# Tracer-1_1.net
KiCad netlist of a schematic drawn in EasyEDA Pro
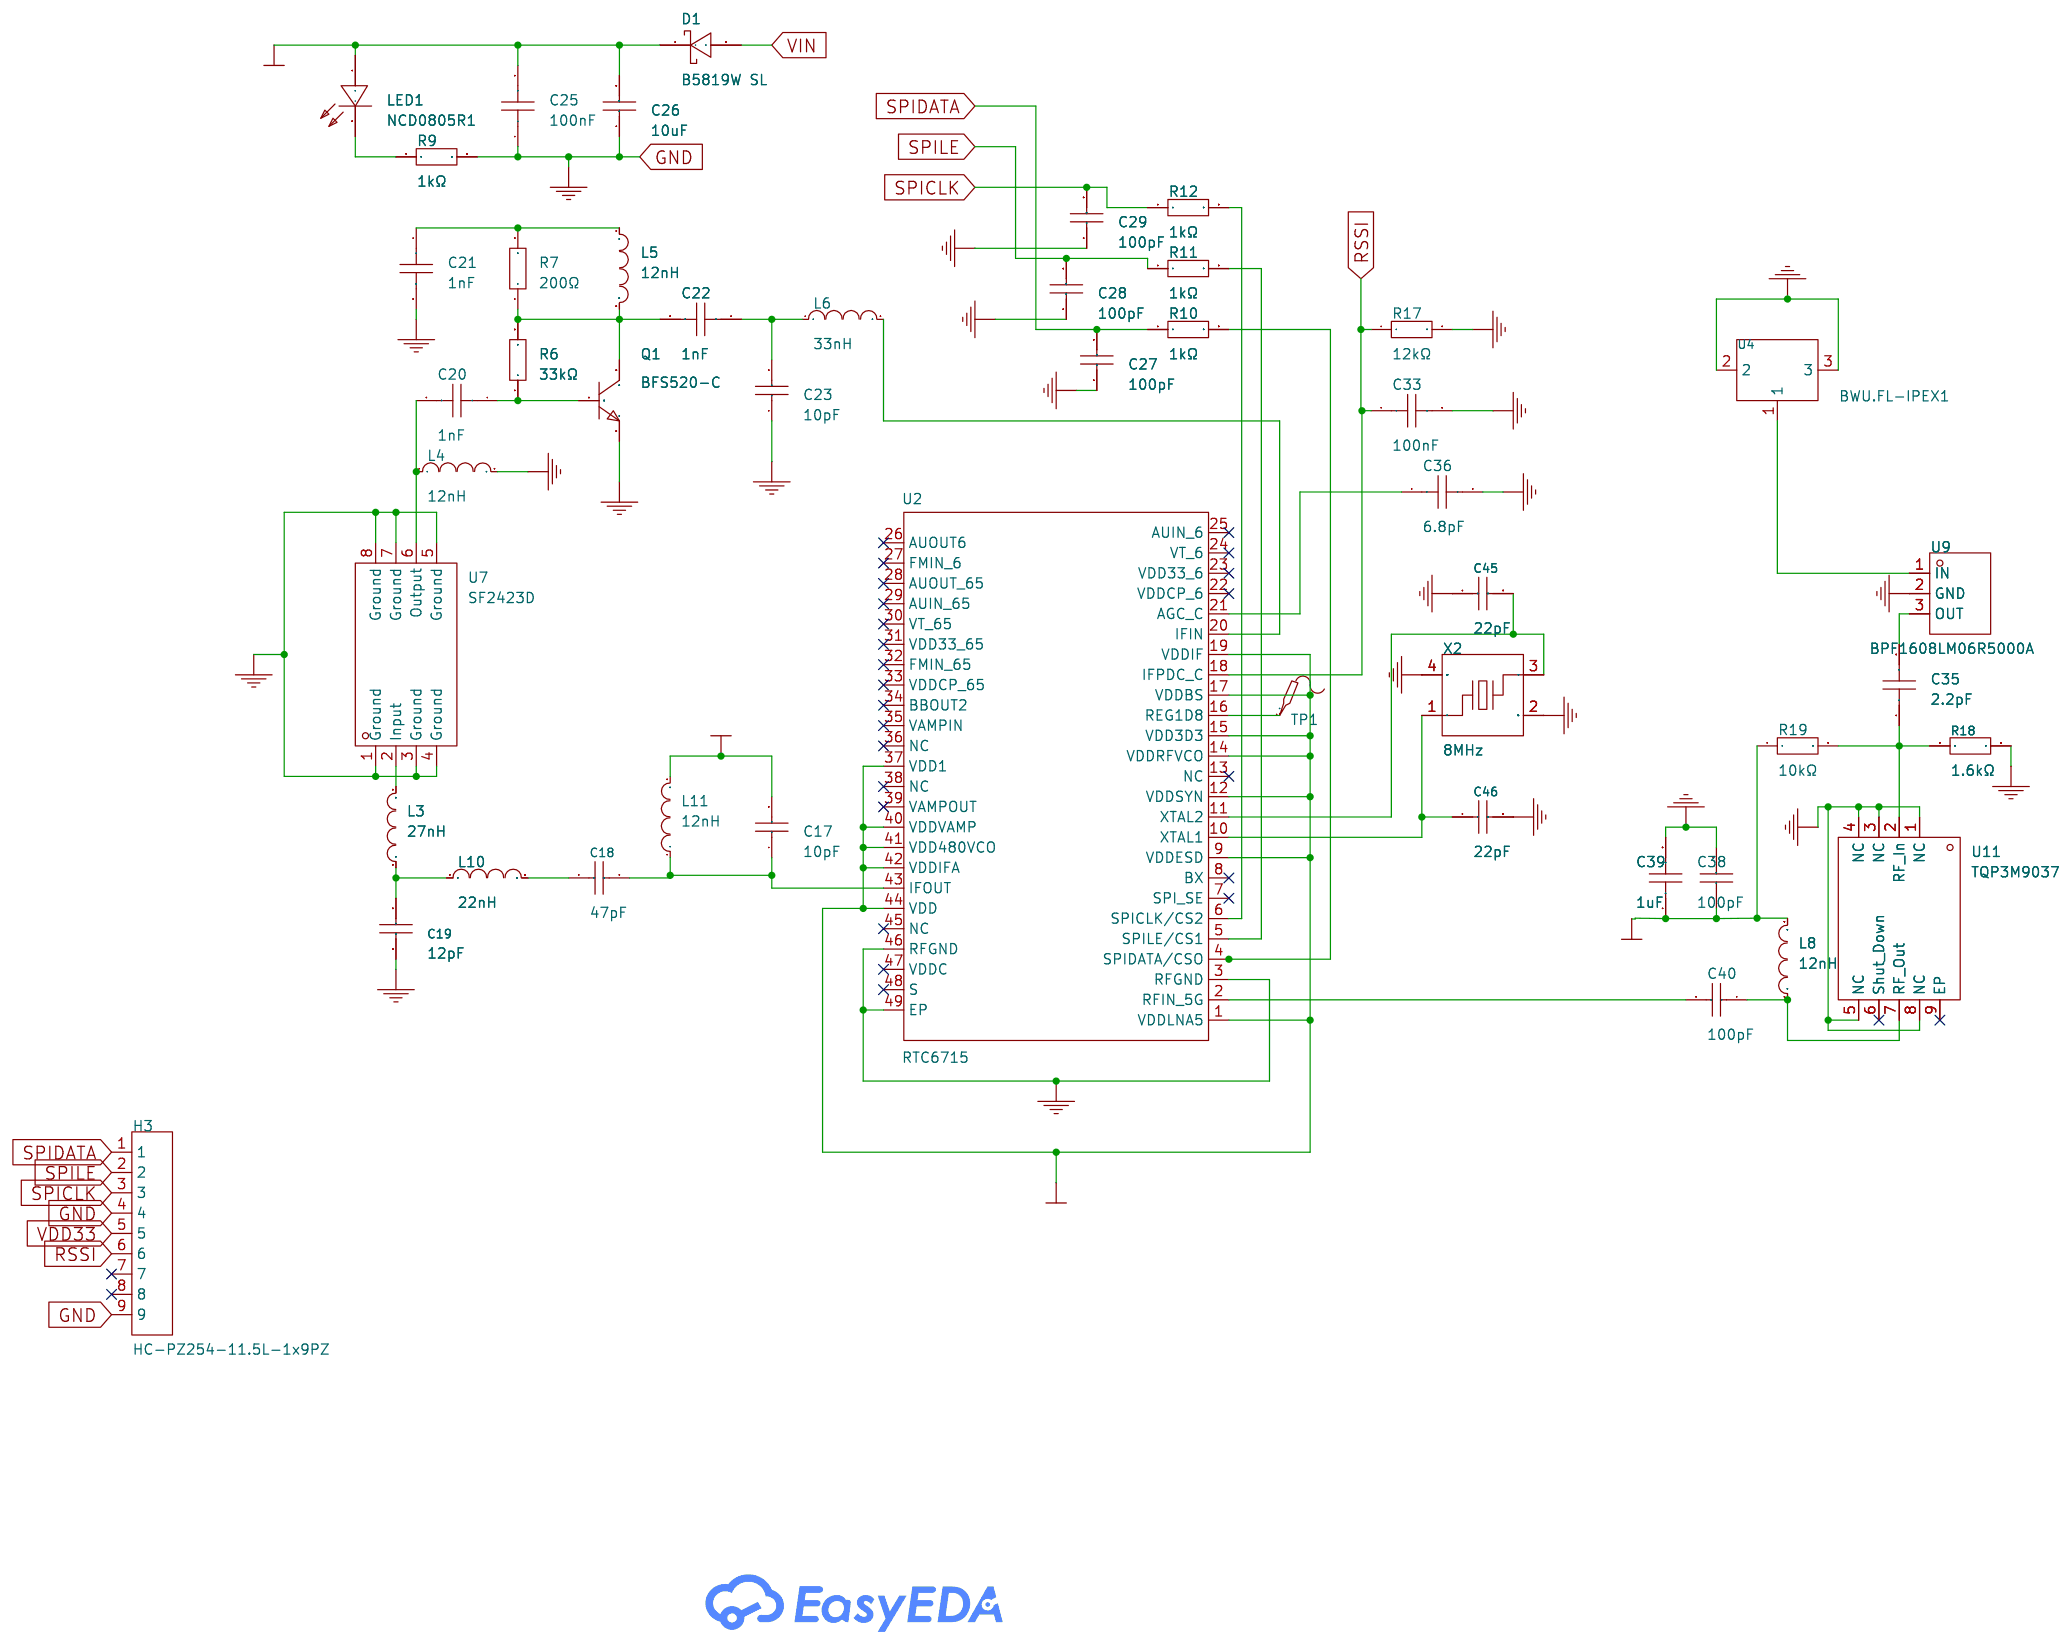
[diagram p0: schematic sheet]

(export (version "E")
  (design (tool "Eeschema 10.0.6"))
  (components
    (comp (ref "C17")
      (value "10pF")
      (footprint "easyedapro:C0402")
      (fields
        (field (name "Manufacturer Part") "CC0402JRNPO9BN100")
        (field (name "Manufacturer") "YAGEO(国巨)")
      )
      (libsource (lib "easyedapro") (part "CC0402JRNPO9BN100"))
    )
    (comp (ref "C18")
      (value "47pF")
      (footprint "easyedapro:C0402")
      (fields
        (field (name "Manufacturer Part") "CC0402JRNPO9BN470")
        (field (name "Manufacturer") "YAGEO(国巨)")
      )
      (libsource (lib "easyedapro") (part "CC0402JRNPO9BN470"))
    )
    (comp (ref "C19")
      (value "12pF")
      (footprint "easyedapro:C0402")
      (fields
        (field (name "Manufacturer Part") "GRM1555C1H120JA01D")
        (field (name "Manufacturer") "muRata(村田)")
      )
      (libsource (lib "easyedapro") (part "GRM1555C1H120JA01D"))
    )
    (comp (ref "C20")
      (value "1nF")
      (footprint "easyedapro:C0402")
      (fields
        (field (name "Manufacturer Part") "GRM155R71H102KA01D")
        (field (name "Manufacturer") "muRata(村田)")
      )
      (libsource (lib "easyedapro") (part "GRM155R71H102KA01D"))
    )
    (comp (ref "C21")
      (value "1nF")
      (footprint "easyedapro:C0402")
      (fields
        (field (name "Manufacturer Part") "GRM155R71H102KA01D")
        (field (name "Manufacturer") "muRata(村田)")
      )
      (libsource (lib "easyedapro") (part "GRM155R71H102KA01D"))
    )
    (comp (ref "C22")
      (value "1nF")
      (footprint "easyedapro:C0402")
      (fields
        (field (name "Manufacturer Part") "GRM155R71H102KA01D")
        (field (name "Manufacturer") "muRata(村田)")
      )
      (libsource (lib "easyedapro") (part "GRM155R71H102KA01D"))
    )
    (comp (ref "C23")
      (value "10pF")
      (footprint "easyedapro:C0402")
      (fields
        (field (name "Manufacturer Part") "GRM1555C1H100JA01D")
        (field (name "Manufacturer") "muRata(村田)")
      )
      (libsource (lib "easyedapro") (part "GRM1555C1H100JA01D"))
    )
    (comp (ref "C25")
      (value "100nF")
      (footprint "easyedapro:C0402")
      (fields
        (field (name "Manufacturer Part") "CL05B104KO5NNNC")
        (field (name "Manufacturer") "SAMSUNG(三星)")
      )
      (libsource (lib "easyedapro") (part "CL05B104KO5NNNC"))
    )
    (comp (ref "C26")
      (value "10uF")
      (fields
        (field (name "Manufacturer Part") "GRM155R60J106ME44D")
        (field (name "Manufacturer") "muRata(村田)")
      )
      (libsource (lib "easyedapro") (part "CL05A106MQ5NUNC"))
    )
    (comp (ref "C27")
      (value "100pF")
      (footprint "easyedapro:C0402")
      (fields
        (field (name "Manufacturer Part") "GRM1555C1H101JA01D")
        (field (name "Manufacturer") "muRata(村田)")
      )
      (libsource (lib "easyedapro") (part "GRM1555C1H101JA01D"))
    )
    (comp (ref "C28")
      (value "100pF")
      (footprint "easyedapro:C0402")
      (fields
        (field (name "Manufacturer Part") "GRM1555C1H101JA01D")
        (field (name "Manufacturer") "muRata(村田)")
      )
      (libsource (lib "easyedapro") (part "GRM1555C1H101JA01D"))
    )
    (comp (ref "C29")
      (value "100pF")
      (footprint "easyedapro:C0402")
      (fields
        (field (name "Manufacturer Part") "GRM1555C1H101JA01D")
        (field (name "Manufacturer") "muRata(村田)")
      )
      (libsource (lib "easyedapro") (part "GRM1555C1H101JA01D"))
    )
    (comp (ref "C33")
      (value "100nF")
      (footprint "easyedapro:C0402")
      (fields
        (field (name "Manufacturer Part") "CL05B104KO5NNNC")
        (field (name "Manufacturer") "SAMSUNG(三星)")
      )
      (libsource (lib "easyedapro") (part "CL05B104KO5NNNC"))
    )
    (comp (ref "C35")
      (value "2.2pF")
      (footprint "easyedapro:C0402")
      (fields
        (field (name "Manufacturer Part") "GJM1555C1H2R2BB01D")
        (field (name "Manufacturer") "muRata(村田)")
      )
      (libsource (lib "easyedapro") (part "GJM1555C1H2R2BB01D"))
    )
    (comp (ref "C36")
      (value "6.8pF")
      (footprint "easyedapro:C0402")
      (fields
        (field (name "Manufacturer Part") "CC0402CRNPO9BN6R8")
        (field (name "Manufacturer") "YAGEO(国巨)")
      )
      (libsource (lib "easyedapro") (part "CC0402CRNPO9BN6R8"))
    )
    (comp (ref "C38")
      (value "100pF")
      (footprint "easyedapro:C0402")
      (fields
        (field (name "Manufacturer Part") "GRM1555C1H101JA01D")
        (field (name "Manufacturer") "muRata(村田)")
      )
      (libsource (lib "easyedapro") (part "GRM1555C1H101JA01D"))
    )
    (comp (ref "C39")
      (value "1uF")
      (footprint "easyedapro:C0402")
      (fields
        (field (name "Manufacturer Part") "CL05A105KA5NQNC")
        (field (name "Manufacturer") "SAMSUNG(三星)")
      )
      (libsource (lib "easyedapro") (part "CL05A105KA5NQNC"))
    )
    (comp (ref "C40")
      (value "100pF")
      (footprint "easyedapro:C0402")
      (fields
        (field (name "Manufacturer Part") "GRM1555C1H101JA01D")
        (field (name "Manufacturer") "muRata(村田)")
      )
      (libsource (lib "easyedapro") (part "GRM1555C1H101JA01D"))
    )
    (comp (ref "C45")
      (value "22pF")
      (footprint "easyedapro:C0402")
      (fields
        (field (name "Manufacturer Part") "CC0402JRNPO9BN220")
        (field (name "Manufacturer") "YAGEO(国巨)")
      )
      (libsource (lib "easyedapro") (part "CC0402JRNPO9BN220"))
    )
    (comp (ref "C46")
      (value "22pF")
      (footprint "easyedapro:C0402")
      (fields
        (field (name "Manufacturer Part") "CC0402JRNPO9BN220")
        (field (name "Manufacturer") "YAGEO(国巨)")
      )
      (libsource (lib "easyedapro") (part "CC0402JRNPO9BN220"))
    )
    (comp (ref "D1")
      (value "B5819W SL")
      (footprint "easyedapro:SOD-123_L2.7-W1.6-LS3.7-RD-1")
      (description "Forward Voltage (Vf@If):600mV@1A Reverse Voltage (Vr):40V Rectified Current:1A")
      (fields (field (name "Manufacturer") "CJ(江苏长电/长晶)"))
      (libsource (lib "easyedapro") (part "B5819W_C8598"))
    )
    (comp (ref "H3")
      (value "HC-PZ254-11.5L-1x9PZ")
      (footprint "easyedapro:HDR-TH_9P-P2.54-V-M")
      (fields (field (name "Manufacturer") "HC(虹成电子)"))
      (libsource (lib "easyedapro") (part "HC-PZ254-11.5L-1X9PZ"))
    )
    (comp (ref "L3")
      (value "27nH")
      (footprint "easyedapro:L0402-RD")
      (fields (field (name "Manufacturer Part") "LQG15HS27NJ02D") (field (name "Manufacturer") "muRata(村田)"))
      (libsource (lib "easyedapro") (part "LQG15HS27NJ02D"))
    )
    (comp (ref "L4")
      (value "12nH")
      (footprint "easyedapro:L0402")
      (fields (field (name "Manufacturer Part") "LQW15AN12NG00D") (field (name "Manufacturer") "muRata(村田)"))
      (libsource (lib "easyedapro") (part "LQW15AN12NG00D"))
    )
    (comp (ref "L5")
      (value "12nH")
      (footprint "easyedapro:L0402")
      (fields (field (name "Manufacturer Part") "LQW15AN12NG00D") (field (name "Manufacturer") "muRata(村田)"))
      (libsource (lib "easyedapro") (part "LQW15AN12NG00D"))
    )
    (comp (ref "L6")
      (value "33nH")
      (footprint "easyedapro:L0402")
      (fields (field (name "Manufacturer Part") "LQG15HS33NJ02D") (field (name "Manufacturer") "muRata(村田)"))
      (libsource (lib "easyedapro") (part "LQG15HS33NJ02D"))
    )
    (comp (ref "L8")
      (value "12nH")
      (footprint "easyedapro:L0402")
      (fields (field (name "Manufacturer Part") "LQW15AN12NG00D") (field (name "Manufacturer") "muRata(村田)"))
      (libsource (lib "easyedapro") (part "LQW15AN12NG00D"))
    )
    (comp (ref "L10")
      (value "22nH")
      (footprint "easyedapro:L0402")
      (fields (field (name "Manufacturer Part") "LQW15AN22NJ00D") (field (name "Manufacturer") "muRata(村田)"))
      (libsource (lib "easyedapro") (part "LQW15AN22NJ00D"))
    )
    (comp (ref "L11")
      (value "12nH")
      (footprint "easyedapro:L0402")
      (fields (field (name "Manufacturer Part") "LQW15AN12NG00D") (field (name "Manufacturer") "muRata(村田)"))
      (libsource (lib "easyedapro") (part "LQW15AN12NG00D"))
    )
    (comp (ref "LED1")
      (value "NCD0805R1")
      (footprint "easyedapro:LED0805-R-RD")
      (fields (field (name "Manufacturer") "国星光电"))
      (libsource (lib "easyedapro") (part "FC-2012HRK-620D"))
    )
    (comp (ref "Q1")
      (value "BFS520-C")
      (footprint "easyedapro:SOT-323-3_L2.0-W1.3-P1.30-LS2.3-BR")
      (fields (field (name "Manufacturer") "Slkor(萨科微)"))
      (libsource (lib "easyedapro") (part "BFS520-C"))
    )
    (comp (ref "R6")
      (value "33kΩ")
      (footprint "easyedapro:R0402")
      (fields (field (name "Manufacturer Part") "RC0402FR-0733KL") (field (name "Manufacturer") "YAGEO(国巨)"))
      (libsource (lib "easyedapro") (part "RC0402FR-0733KL"))
    )
    (comp (ref "R7")
      (value "200Ω")
      (footprint "easyedapro:R0402")
      (fields (field (name "Manufacturer Part") "RC0402FR-07200RL") (field (name "Manufacturer") "YAGEO(国巨)"))
      (libsource (lib "easyedapro") (part "RC0402FR-07200RL"))
    )
    (comp (ref "R9")
      (value "1kΩ")
      (footprint "easyedapro:R0402")
      (fields (field (name "Manufacturer Part") "RC0402FR-071KL") (field (name "Manufacturer") "YAGEO(国巨)"))
      (libsource (lib "easyedapro") (part "RC0402FR-071KL"))
    )
    (comp (ref "R10")
      (value "1kΩ")
      (footprint "easyedapro:R0402")
      (fields (field (name "Manufacturer Part") "RC0402FR-071KL") (field (name "Manufacturer") "YAGEO(国巨)"))
      (libsource (lib "easyedapro") (part "RC0402FR-071KL"))
    )
    (comp (ref "R11")
      (value "1kΩ")
      (footprint "easyedapro:R0402")
      (fields (field (name "Manufacturer Part") "RC0402FR-071KL") (field (name "Manufacturer") "YAGEO(国巨)"))
      (libsource (lib "easyedapro") (part "RC0402FR-071KL"))
    )
    (comp (ref "R12")
      (value "1kΩ")
      (footprint "easyedapro:R0402")
      (fields (field (name "Manufacturer Part") "RC0402FR-071KL") (field (name "Manufacturer") "YAGEO(国巨)"))
      (libsource (lib "easyedapro") (part "RC0402FR-071KL"))
    )
    (comp (ref "R17")
      (value "12kΩ")
      (footprint "easyedapro:R0402")
      (fields (field (name "Manufacturer Part") "RTT021202FTH") (field (name "Manufacturer") "RALEC(旺诠)"))
      (libsource (lib "easyedapro") (part "RTT021202FTH"))
    )
    (comp (ref "R18")
      (value "1.6kΩ")
      (footprint "easyedapro:R0402")
      (fields
        (field (name "Manufacturer Part") "0402WGF1601TCE")
        (field (name "Manufacturer") "UNI-ROYAL(厚声)")
      )
      (libsource (lib "easyedapro") (part "0402WGF1601TCE"))
    )
    (comp (ref "R19")
      (value "10kΩ")
      (footprint "easyedapro:R0402")
      (fields
        (field (name "Manufacturer Part") "0402WGF1002TCE")
        (field (name "Manufacturer") "UNI-ROYAL(厚声)")
      )
      (libsource (lib "easyedapro") (part "0402WGF1002TCE"))
    )
    (comp (ref "TP1")
      (value "~")
      (footprint "easyedapro:Test-Point-0.5mm")
      (description "Test Point 测试点")
      (libsource (lib "easyedapro") (part "Test-Point"))
    )
    (comp (ref "U2") (value "RTC6715") (libsource (lib "easyedapro") (part "RTC6715")))
    (comp (ref "U4")
      (value "BWU.FL-IPEX1")
      (footprint "easyedapro:IPEX-SMD_BWIPX-1-001E")
      (fields (field (name "Manufacturer") "BAT WIRELESS(蝙蝠无线)"))
      (libsource (lib "easyedapro") (part "BWU.FL-IPEX1"))
    )
    (comp (ref "U7")
      (value "SF2423D")
      (footprint "easyedapro:FILTER-SMD_8P-L3.8-W3.8-P1.27-BL")
      (fields (field (name "Manufacturer") "muRata(村田)"))
      (libsource (lib "easyedapro") (part "SF2423D"))
    )
    (comp (ref "U9")
      (value "BPF1608LM06R5000A")
      (footprint "easyedapro:FILTER-SMD_3P-L1.6-W0.8-L")
      (description "Bandwidth:800MHz Filter Type:Bandpass Insertion Loss:0.6dB")
      (fields (field (name "Manufacturer") "YAGEO(国巨)"))
      (libsource (lib "easyedapro") (part "BPF1608LM06R5000A"))
    )
    (comp (ref "U11")
      (value "TQP3M9037")
      (footprint "easyedapro:DFN-8_L2.0-W2.0-P0.50-BL-EP")
      (fields (field (name "Manufacturer") "Qorvo"))
      (libsource (lib "easyedapro") (part "TQP3M9037"))
    )
    (comp (ref "X2")
      (value "8MHz")
      (footprint "easyedapro:CRYSTAL-SMD_4P-L3.2-W2.5-BL")
      (fields (field (name "Manufacturer Part") "K3A080001210") (field (name "Manufacturer") "KYX(凯越翔)"))
      (libsource (lib "easyedapro") (part "K3A080001210"))
    )
  )
  (nets
    (net (code "1") (name "GND") (class "Default")
      (node (ref "C19") (pin "1") (pinfunction "1_1") (pintype "input"))
      (node (ref "C21") (pin "2") (pinfunction "2_2") (pintype "unspecified"))
      (node (ref "C23") (pin "1") (pinfunction "1_1") (pintype "input"))
      (node (ref "C25") (pin "1") (pinfunction "1_1") (pintype "unspecified"))
      (node (ref "C26") (pin "1") (pinfunction "1_1") (pintype "input"))
      (node (ref "C27") (pin "1") (pinfunction "1_1") (pintype "input"))
      (node (ref "C28") (pin "1") (pinfunction "1_1") (pintype "input"))
      (node (ref "C29") (pin "1") (pinfunction "1_1") (pintype "input"))
      (node (ref "C33") (pin "2") (pinfunction "2_2") (pintype "unspecified"))
      (node (ref "C36") (pin "2") (pinfunction "2_2") (pintype "unspecified"))
      (node (ref "C38") (pin "2") (pinfunction "2_2") (pintype "input"))
      (node (ref "C39") (pin "2") (pinfunction "2_2") (pintype "unspecified"))
      (node (ref "C45") (pin "1") (pinfunction "1_1") (pintype "input"))
      (node (ref "C46") (pin "2") (pinfunction "2_2") (pintype "input"))
      (node (ref "H3") (pin "4") (pinfunction "4_4") (pintype "unspecified"))
      (node (ref "H3") (pin "9") (pinfunction "9_9") (pintype "unspecified"))
      (node (ref "L4") (pin "2") (pinfunction "2_2") (pintype "unspecified"))
      (node (ref "Q1") (pin "2") (pinfunction "E_2") (pintype "input"))
      (node (ref "R17") (pin "2") (pinfunction "2_2") (pintype "input"))
      (node (ref "R18") (pin "2") (pinfunction "2_2") (pintype "input"))
      (node (ref "R9") (pin "2") (pinfunction "2_2") (pintype "input"))
      (node (ref "U11") (pin "1") (pinfunction "NC_1") (pintype "unspecified"))
      (node (ref "U11") (pin "3") (pinfunction "NC_3") (pintype "unspecified"))
      (node (ref "U11") (pin "4") (pinfunction "NC_4") (pintype "unspecified"))
      (node (ref "U11") (pin "5") (pinfunction "NC_5") (pintype "unspecified"))
      (node (ref "U11") (pin "8") (pinfunction "NC_8") (pintype "unspecified"))
      (node (ref "U2") (pin "3") (pinfunction "RFGND_3") (pintype "unspecified"))
      (node (ref "U2") (pin "46") (pinfunction "RFGND_46") (pintype "unspecified"))
      (node (ref "U2") (pin "49") (pinfunction "EP_49") (pintype "unspecified"))
      (node (ref "U4") (pin "2") (pinfunction "2_2") (pintype "input"))
      (node (ref "U4") (pin "3") (pinfunction "3_3") (pintype "input"))
      (node (ref "U7") (pin "1") (pinfunction "Ground_1") (pintype "unspecified"))
      (node (ref "U7") (pin "3") (pinfunction "Ground_3") (pintype "unspecified"))
      (node (ref "U7") (pin "4") (pinfunction "Ground_4") (pintype "unspecified"))
      (node (ref "U7") (pin "5") (pinfunction "Ground_5") (pintype "unspecified"))
      (node (ref "U7") (pin "7") (pinfunction "Ground_7") (pintype "unspecified"))
      (node (ref "U7") (pin "8") (pinfunction "Ground_8") (pintype "unspecified"))
      (node (ref "U9") (pin "2") (pinfunction "GND_2") (pintype "unspecified"))
      (node (ref "X2") (pin "2") (pinfunction "GND_2") (pintype "input"))
      (node (ref "X2") (pin "4") (pinfunction "GND_4") (pintype "input"))
    )
    (net (code "2") (name "Net-(C18-Pad1)") (class "Default")
      (node (ref "C18") (pin "1") (pinfunction "1_1") (pintype "input"))
      (node (ref "L10") (pin "2") (pinfunction "2_2") (pintype "unspecified"))
    )
    (net (code "3") (name "Net-(C19-Pad2)") (class "Default")
      (node (ref "C19") (pin "2") (pinfunction "2_2") (pintype "input"))
      (node (ref "L10") (pin "1") (pinfunction "1_1") (pintype "unspecified"))
      (node (ref "L3") (pin "1") (pinfunction "1_1") (pintype "unspecified"))
    )
    (net (code "4") (name "Net-(C21-Pad1)") (class "Default")
      (node (ref "C21") (pin "1") (pinfunction "1_1") (pintype "unspecified"))
      (node (ref "L5") (pin "1") (pinfunction "1_1") (pintype "unspecified"))
      (node (ref "R7") (pin "2") (pinfunction "2_2") (pintype "input"))
    )
    (net (code "5") (name "Net-(C22-Pad1)") (class "Default")
      (node (ref "C22") (pin "1") (pinfunction "1_1") (pintype "unspecified"))
      (node (ref "C23") (pin "2") (pinfunction "2_2") (pintype "input"))
      (node (ref "L6") (pin "1") (pinfunction "1_1") (pintype "unspecified"))
    )
    (net (code "6") (name "Net-(LED1--)") (class "Default")
      (node (ref "LED1") (pin "2") (pinfunction "-_2") (pintype "unspecified"))
      (node (ref "R9") (pin "1") (pinfunction "1_1") (pintype "input"))
    )
    (net (code "7") (name "Net-(Q1-B)") (class "Default")
      (node (ref "C20") (pin "1") (pinfunction "1_1") (pintype "unspecified"))
      (node (ref "Q1") (pin "1") (pinfunction "B_1") (pintype "input"))
      (node (ref "R6") (pin "1") (pinfunction "1_1") (pintype "input"))
    )
    (net (code "8") (name "Net-(Q1-C)") (class "Default")
      (node (ref "C22") (pin "2") (pinfunction "2_2") (pintype "unspecified"))
      (node (ref "L5") (pin "2") (pinfunction "2_2") (pintype "unspecified"))
      (node (ref "Q1") (pin "3") (pinfunction "C_3") (pintype "input"))
      (node (ref "R6") (pin "2") (pinfunction "2_2") (pintype "input"))
      (node (ref "R7") (pin "1") (pinfunction "1_1") (pintype "input"))
    )
    (net (code "9") (name "Net-(U2-AGC_C)") (class "Default")
      (node (ref "C36") (pin "1") (pinfunction "1_1") (pintype "unspecified"))
      (node (ref "U2") (pin "21") (pinfunction "AGC_C_21") (pintype "unspecified"))
    )
    (net (code "10") (name "Net-(U2-IFIN)") (class "Default")
      (node (ref "L6") (pin "2") (pinfunction "2_2") (pintype "unspecified"))
      (node (ref "U2") (pin "20") (pinfunction "IFIN_20") (pintype "unspecified"))
    )
    (net (code "11") (name "Net-(U2-IFOUT)") (class "Default")
      (node (ref "C17") (pin "1") (pinfunction "1_1") (pintype "input"))
      (node (ref "C18") (pin "2") (pinfunction "2_2") (pintype "input"))
      (node (ref "L11") (pin "1") (pinfunction "1_1") (pintype "unspecified"))
      (node (ref "U2") (pin "43") (pinfunction "IFOUT_43") (pintype "unspecified"))
    )
    (net (code "12") (name "Net-(U2-REG1D8)") (class "Default")
      (node (ref "TP1") (pin "1") (pinfunction "1_1") (pintype "unspecified"))
      (node (ref "U2") (pin "16") (pinfunction "REG1D8_16") (pintype "unspecified"))
    )
    (net (code "13") (name "Net-(U2-RFIN_5G)") (class "Default")
      (node (ref "C40") (pin "2") (pinfunction "2_2") (pintype "input"))
      (node (ref "U2") (pin "2") (pinfunction "RFIN_5G_2") (pintype "unspecified"))
    )
    (net (code "14") (name "Net-(U2-SPICLK{slash}CS2)") (class "Default")
      (node (ref "R12") (pin "2") (pinfunction "2_2") (pintype "input"))
      (node (ref "U2") (pin "6") (pinfunction "SPICLK/CS2_6") (pintype "unspecified"))
    )
    (net (code "15") (name "Net-(U2-SPIDATA{slash}CSO)") (class "Default")
      (node (ref "R10") (pin "2") (pinfunction "2_2") (pintype "input"))
      (node (ref "U2") (pin "4") (pinfunction "SPIDATA/CSO_4") (pintype "unspecified"))
    )
    (net (code "16") (name "Net-(U2-SPILE{slash}CS1)") (class "Default")
      (node (ref "R11") (pin "2") (pinfunction "2_2") (pintype "input"))
      (node (ref "U2") (pin "5") (pinfunction "SPILE/CS1_5") (pintype "unspecified"))
    )
    (net (code "17") (name "Net-(U2-XTAL1)") (class "Default")
      (node (ref "C46") (pin "1") (pinfunction "1_1") (pintype "input"))
      (node (ref "U2") (pin "10") (pinfunction "XTAL1_10") (pintype "unspecified"))
      (node (ref "X2") (pin "1") (pinfunction "1_1") (pintype "input"))
    )
    (net (code "18") (name "Net-(U2-XTAL2)") (class "Default")
      (node (ref "C45") (pin "2") (pinfunction "2_2") (pintype "input"))
      (node (ref "U2") (pin "11") (pinfunction "XTAL2_11") (pintype "unspecified"))
      (node (ref "X2") (pin "3") (pinfunction "3_3") (pintype "input"))
    )
    (net (code "19") (name "Net-(U7-Input)") (class "Default")
      (node (ref "L3") (pin "2") (pinfunction "2_2") (pintype "unspecified"))
      (node (ref "U7") (pin "2") (pinfunction "Input_2") (pintype "unspecified"))
    )
    (net (code "20") (name "Net-(U7-Output)") (class "Default")
      (node (ref "C20") (pin "2") (pinfunction "2_2") (pintype "unspecified"))
      (node (ref "L4") (pin "1") (pinfunction "1_1") (pintype "unspecified"))
      (node (ref "U7") (pin "6") (pinfunction "Output_6") (pintype "unspecified"))
    )
    (net (code "21") (name "Net-(U9-IN)") (class "Default")
      (node (ref "U4") (pin "1") (pinfunction "1_1") (pintype "input"))
      (node (ref "U9") (pin "1") (pinfunction "IN_1") (pintype "unspecified"))
    )
    (net (code "22") (name "Net-(U9-OUT)") (class "Default")
      (node (ref "C35") (pin "2") (pinfunction "2_2") (pintype "unspecified"))
      (node (ref "U9") (pin "3") (pinfunction "OUT_3") (pintype "unspecified"))
    )
    (net (code "23") (name "Net-(U11-RF_In)") (class "Default")
      (node (ref "C35") (pin "1") (pinfunction "1_1") (pintype "unspecified"))
      (node (ref "R18") (pin "1") (pinfunction "1_1") (pintype "input"))
      (node (ref "R19") (pin "2") (pinfunction "2_2") (pintype "input"))
      (node (ref "U11") (pin "2") (pinfunction "RF_In_2") (pintype "unspecified"))
    )
    (net (code "24") (name "Net-(U11-RF_Out)") (class "Default")
      (node (ref "C40") (pin "1") (pinfunction "1_1") (pintype "input"))
      (node (ref "L8") (pin "1") (pinfunction "1_1") (pintype "unspecified"))
      (node (ref "U11") (pin "7") (pinfunction "RF_Out_7") (pintype "unspecified"))
    )
    (net (code "25") (name "RSSI") (class "Default")
      (node (ref "C33") (pin "1") (pinfunction "1_1") (pintype "unspecified"))
      (node (ref "H3") (pin "6") (pinfunction "6_6") (pintype "unspecified"))
      (node (ref "R17") (pin "1") (pinfunction "1_1") (pintype "input"))
      (node (ref "U2") (pin "18") (pinfunction "IFPDC_C_18") (pintype "unspecified"))
    )
    (net (code "26") (name "SPICLK") (class "Default")
      (node (ref "C29") (pin "2") (pinfunction "2_2") (pintype "input"))
      (node (ref "H3") (pin "3") (pinfunction "3_3") (pintype "unspecified"))
      (node (ref "R12") (pin "1") (pinfunction "1_1") (pintype "input"))
    )
    (net (code "27") (name "SPIDATA") (class "Default")
      (node (ref "C27") (pin "2") (pinfunction "2_2") (pintype "input"))
      (node (ref "H3") (pin "1") (pinfunction "1_1") (pintype "unspecified"))
      (node (ref "R10") (pin "1") (pinfunction "1_1") (pintype "input"))
    )
    (net (code "28") (name "SPILE") (class "Default")
      (node (ref "C28") (pin "2") (pinfunction "2_2") (pintype "input"))
      (node (ref "H3") (pin "2") (pinfunction "2_2") (pintype "unspecified"))
      (node (ref "R11") (pin "1") (pinfunction "1_1") (pintype "input"))
    )
    (net (code "29") (name "VDD33") (class "Default")
      (node (ref "C17") (pin "2") (pinfunction "2_2") (pintype "input"))
      (node (ref "C25") (pin "2") (pinfunction "2_2") (pintype "unspecified"))
      (node (ref "C26") (pin "2") (pinfunction "2_2") (pintype "input"))
      (node (ref "C38") (pin "1") (pinfunction "1_1") (pintype "input"))
      (node (ref "C39") (pin "1") (pinfunction "1_1") (pintype "unspecified"))
      (node (ref "D1") (pin "1") (pinfunction "-_1") (pintype "unspecified"))
      (node (ref "H3") (pin "5") (pinfunction "5_5") (pintype "unspecified"))
      (node (ref "L11") (pin "2") (pinfunction "2_2") (pintype "unspecified"))
      (node (ref "LED1") (pin "1") (pinfunction "+_1") (pintype "unspecified"))
      (node (ref "R19") (pin "1") (pinfunction "1_1") (pintype "input"))
      (node (ref "U2") (pin "1") (pinfunction "VDDLNA5_1") (pintype "unspecified"))
      (node (ref "U2") (pin "12") (pinfunction "VDDSYN_12") (pintype "unspecified"))
      (node (ref "U2") (pin "14") (pinfunction "VDDRFVCO_14") (pintype "unspecified"))
      (node (ref "U2") (pin "15") (pinfunction "VDD3D3_15") (pintype "unspecified"))
      (node (ref "U2") (pin "17") (pinfunction "VDDBS_17") (pintype "unspecified"))
      (node (ref "U2") (pin "19") (pinfunction "VDDIF_19") (pintype "unspecified"))
      (node (ref "U2") (pin "37") (pinfunction "VDD1_37") (pintype "unspecified"))
      (node (ref "U2") (pin "40") (pinfunction "VDDVAMP_40") (pintype "unspecified"))
      (node (ref "U2") (pin "41") (pinfunction "VDD480VCO_41") (pintype "unspecified"))
      (node (ref "U2") (pin "42") (pinfunction "VDDIFA_42") (pintype "unspecified"))
      (node (ref "U2") (pin "44") (pinfunction "VDD_44") (pintype "unspecified"))
      (node (ref "U2") (pin "9") (pinfunction "VDDESD_9") (pintype "unspecified"))
    )
    (net (code "30") (name "VIN") (class "Default")
      (node (ref "D1") (pin "2") (pinfunction "+_2") (pintype "unspecified"))
    )
    (net (code "31") (name "unconnected-(H3-Pad7)") (class "Default")
      (node (ref "H3") (pin "7") (pinfunction "7_7") (pintype "unspecified+no_connect"))
    )
    (net (code "32") (name "unconnected-(H3-Pad8)") (class "Default")
      (node (ref "H3") (pin "8") (pinfunction "8_8") (pintype "unspecified+no_connect"))
    )
    (net (code "33") (name "unconnected-(L8-Pad2)") (class "Default")
      (node (ref "L8") (pin "2") (pinfunction "2_2") (pintype "unspecified"))
    )
    (net (code "34") (name "unconnected-(U2-AUIN_6-Pad25)") (class "Default")
      (node (ref "U2") (pin "25") (pinfunction "AUIN_6_25") (pintype "unspecified+no_connect"))
    )
    (net (code "35") (name "unconnected-(U2-AUIN_65-Pad29)") (class "Default")
      (node (ref "U2") (pin "29") (pinfunction "AUIN_65_29") (pintype "unspecified+no_connect"))
    )
    (net (code "36") (name "unconnected-(U2-AUOUT6-Pad26)") (class "Default")
      (node (ref "U2") (pin "26") (pinfunction "AUOUT6_26") (pintype "unspecified+no_connect"))
    )
    (net (code "37") (name "unconnected-(U2-AUOUT_65-Pad28)") (class "Default")
      (node (ref "U2") (pin "28") (pinfunction "AUOUT_65_28") (pintype "unspecified+no_connect"))
    )
    (net (code "38") (name "unconnected-(U2-BBOUT2-Pad34)") (class "Default")
      (node (ref "U2") (pin "34") (pinfunction "BBOUT2_34") (pintype "unspecified+no_connect"))
    )
    (net (code "39") (name "unconnected-(U2-BX-Pad8)") (class "Default")
      (node (ref "U2") (pin "8") (pinfunction "BX_8") (pintype "unspecified+no_connect"))
    )
    (net (code "40") (name "unconnected-(U2-FMIN_6-Pad27)") (class "Default")
      (node (ref "U2") (pin "27") (pinfunction "FMIN_6_27") (pintype "unspecified+no_connect"))
    )
    (net (code "41") (name "unconnected-(U2-FMIN_65-Pad32)") (class "Default")
      (node (ref "U2") (pin "32") (pinfunction "FMIN_65_32") (pintype "unspecified+no_connect"))
    )
    (net (code "42") (name "unconnected-(U2-NC-Pad13)") (class "Default")
      (node (ref "U2") (pin "13") (pinfunction "NC_13") (pintype "unspecified+no_connect"))
    )
    (net (code "43") (name "unconnected-(U2-NC-Pad36)") (class "Default")
      (node (ref "U2") (pin "36") (pinfunction "NC_36") (pintype "unspecified+no_connect"))
    )
    (net (code "44") (name "unconnected-(U2-NC-Pad38)") (class "Default")
      (node (ref "U2") (pin "38") (pinfunction "NC_38") (pintype "unspecified+no_connect"))
    )
    (net (code "45") (name "unconnected-(U2-NC-Pad45)") (class "Default")
      (node (ref "U2") (pin "45") (pinfunction "NC_45") (pintype "unspecified+no_connect"))
    )
    (net (code "46") (name "unconnected-(U2-S-Pad48)") (class "Default")
      (node (ref "U2") (pin "48") (pinfunction "S_48") (pintype "unspecified+no_connect"))
    )
    (net (code "47") (name "unconnected-(U2-SPI_SE-Pad7)") (class "Default")
      (node (ref "U2") (pin "7") (pinfunction "SPI_SE_7") (pintype "unspecified+no_connect"))
    )
    (net (code "48") (name "unconnected-(U2-VAMPIN-Pad35)") (class "Default")
      (node (ref "U2") (pin "35") (pinfunction "VAMPIN_35") (pintype "unspecified+no_connect"))
    )
    (net (code "49") (name "unconnected-(U2-VAMPOUT-Pad39)") (class "Default")
      (node (ref "U2") (pin "39") (pinfunction "VAMPOUT_39") (pintype "unspecified+no_connect"))
    )
    (net (code "50") (name "unconnected-(U2-VDD33_6-Pad23)") (class "Default")
      (node (ref "U2") (pin "23") (pinfunction "VDD33_6_23") (pintype "unspecified+no_connect"))
    )
    (net (code "51") (name "unconnected-(U2-VDD33_65-Pad31)") (class "Default")
      (node (ref "U2") (pin "31") (pinfunction "VDD33_65_31") (pintype "unspecified+no_connect"))
    )
    (net (code "52") (name "unconnected-(U2-VDDC-Pad47)") (class "Default")
      (node (ref "U2") (pin "47") (pinfunction "VDDC_47") (pintype "unspecified+no_connect"))
    )
    (net (code "53") (name "unconnected-(U2-VDDCP_6-Pad22)") (class "Default")
      (node (ref "U2") (pin "22") (pinfunction "VDDCP_6_22") (pintype "unspecified+no_connect"))
    )
    (net (code "54") (name "unconnected-(U2-VDDCP_65-Pad33)") (class "Default")
      (node (ref "U2") (pin "33") (pinfunction "VDDCP_65_33") (pintype "unspecified+no_connect"))
    )
    (net (code "55") (name "unconnected-(U2-VT_6-Pad24)") (class "Default")
      (node (ref "U2") (pin "24") (pinfunction "VT_6_24") (pintype "unspecified+no_connect"))
    )
    (net (code "56") (name "unconnected-(U2-VT_65-Pad30)") (class "Default")
      (node (ref "U2") (pin "30") (pinfunction "VT_65_30") (pintype "unspecified+no_connect"))
    )
    (net (code "57") (name "unconnected-(U11-EP-Pad9)") (class "Default")
      (node (ref "U11") (pin "9") (pinfunction "EP_9") (pintype "unspecified+no_connect"))
    )
    (net (code "58") (name "unconnected-(U11-Shut_Down-Pad6)") (class "Default")
      (node (ref "U11") (pin "6") (pinfunction "Shut_Down_6") (pintype "unspecified+no_connect"))
    )
  )
)
